# CaRe_Schematic_SMD_FRONT_PANEL.net
KiCad netlist of a schematic drawn in Altium Designer
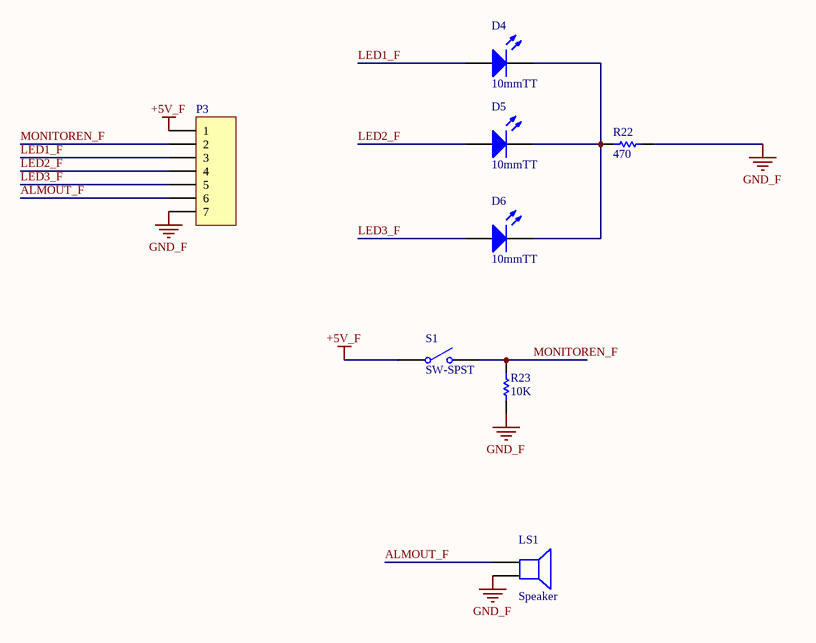
[diagram p0: CaRe_Schematic_SMD_FRONT_PANEL.SchDoc]

(export (version "E")
  (design (tool "Eeschema 10.0.6"))
  (components
    (comp (ref "D4")
      (value "10mmTT")
      (footprint "10mmLED")
      (description "Typical RED LED")
      (fields (field (name "PART NUMBER") "P_100_LTST-C170KRKT") (field (name "PUBLISHER") "Altium Limited"))
      (libsource (lib "CaRe_SchematicLib") (part "10mmLED"))
    )
    (comp (ref "D5")
      (value "10mmTT")
      (footprint "10mmLED")
      (description "Typical RED LED")
      (fields (field (name "PART NUMBER") "P_100_LTST-C170KRKT") (field (name "PUBLISHER") "Altium Limited"))
      (libsource (lib "CaRe_SchematicLib") (part "10mmLED"))
    )
    (comp (ref "D6")
      (value "10mmTT")
      (footprint "10mmLED")
      (description "Typical RED LED")
      (fields (field (name "PART NUMBER") "P_100_LTST-C170KRKT") (field (name "PUBLISHER") "Altium Limited"))
      (libsource (lib "CaRe_SchematicLib") (part "10mmLED"))
    )
    (comp (ref "LS1")
      (value "Speaker")
      (footprint "HDR1X2")
      (description "Loudspeaker")
      (fields (field (name "PUBLISHER") "Altium Limited"))
      (libsource (lib "Miscellaneous Devices") (part "Speaker"))
    )
    (comp (ref "P3")
      (value "Header 7")
      (footprint "HDR1X7")
      (description "Header, 7-Pin")
      (fields (field (name "PUBLISHER") "Altium Limited"))
      (libsource (lib "CaRe_SchematicLib") (part "Header 7"))
    )
    (comp (ref "R22")
      (value "470")
      (footprint "RES0805")
      (description "Resistor")
      (fields (field (name "PUBLISHER") "Altium Limited"))
      (libsource (lib "CaRe_SchematicLib") (part "Chip Res"))
    )
    (comp (ref "R23")
      (value "10K")
      (footprint "RES0805")
      (description "Resistor")
      (fields (field (name "PUBLISHER") "Altium Limited"))
      (libsource (lib "CaRe_SchematicLib") (part "Chip Res"))
    )
    (comp (ref "S1")
      (value "SW-SPST")
      (footprint "SPST")
      (description "Single-Pole, Single-Throw Switch")
      (fields (field (name "PUBLISHER") "Altium Limited"))
      (libsource (lib "Miscellaneous Devices") (part "SW-SPST"))
    )
  )
  (nets
    (net (code "1") (name "+5V_F") (class "Default")
      (node (ref "P3") (pin "1") (pinfunction "1_1") (pintype "passive"))
      (node (ref "S1") (pin "1") (pinfunction "COMMON_1") (pintype "passive"))
    )
    (net (code "2") (name "/ALMOUT_F") (class "Default")
      (node (ref "LS1") (pin "1") (pinfunction "1_1") (pintype "passive"))
      (node (ref "P3") (pin "6") (pinfunction "6_6") (pintype "passive"))
    )
    (net (code "3") (name "/LED1_F") (class "Default")
      (node (ref "D4") (pin "1") (pinfunction "A_1") (pintype "passive"))
      (node (ref "P3") (pin "3") (pinfunction "3_3") (pintype "passive"))
    )
    (net (code "4") (name "/LED2_F") (class "Default")
      (node (ref "D5") (pin "1") (pinfunction "A_1") (pintype "passive"))
      (node (ref "P3") (pin "4") (pinfunction "4_4") (pintype "passive"))
    )
    (net (code "5") (name "/LED3_F") (class "Default")
      (node (ref "D6") (pin "1") (pinfunction "A_1") (pintype "passive"))
      (node (ref "P3") (pin "5") (pinfunction "5_5") (pintype "passive"))
    )
    (net (code "6") (name "/MONITOREN_F") (class "Default")
      (node (ref "P3") (pin "2") (pinfunction "2_2") (pintype "passive"))
      (node (ref "R23") (pin "2") (pinfunction "2_2") (pintype "passive"))
      (node (ref "S1") (pin "2") (pinfunction "NO_2") (pintype "passive"))
    )
    (net (code "7") (name "GND_F") (class "Default")
      (node (ref "LS1") (pin "2") (pinfunction "2_2") (pintype "passive"))
      (node (ref "P3") (pin "7") (pinfunction "7_7") (pintype "passive"))
      (node (ref "R22") (pin "2") (pinfunction "2_2") (pintype "passive"))
      (node (ref "R23") (pin "1") (pinfunction "1_1") (pintype "passive"))
    )
    (net (code "8") (name "Net-(D4-K)") (class "Default")
      (node (ref "D4") (pin "2") (pinfunction "K_2") (pintype "passive"))
      (node (ref "D5") (pin "2") (pinfunction "K_2") (pintype "passive"))
      (node (ref "D6") (pin "2") (pinfunction "K_2") (pintype "passive"))
      (node (ref "R22") (pin "1") (pinfunction "1_1") (pintype "passive"))
    )
  )
)
